# openSX70_chocolate_V341_20180103_manuall.net
KiCad netlist of a schematic drawn in EAGLE
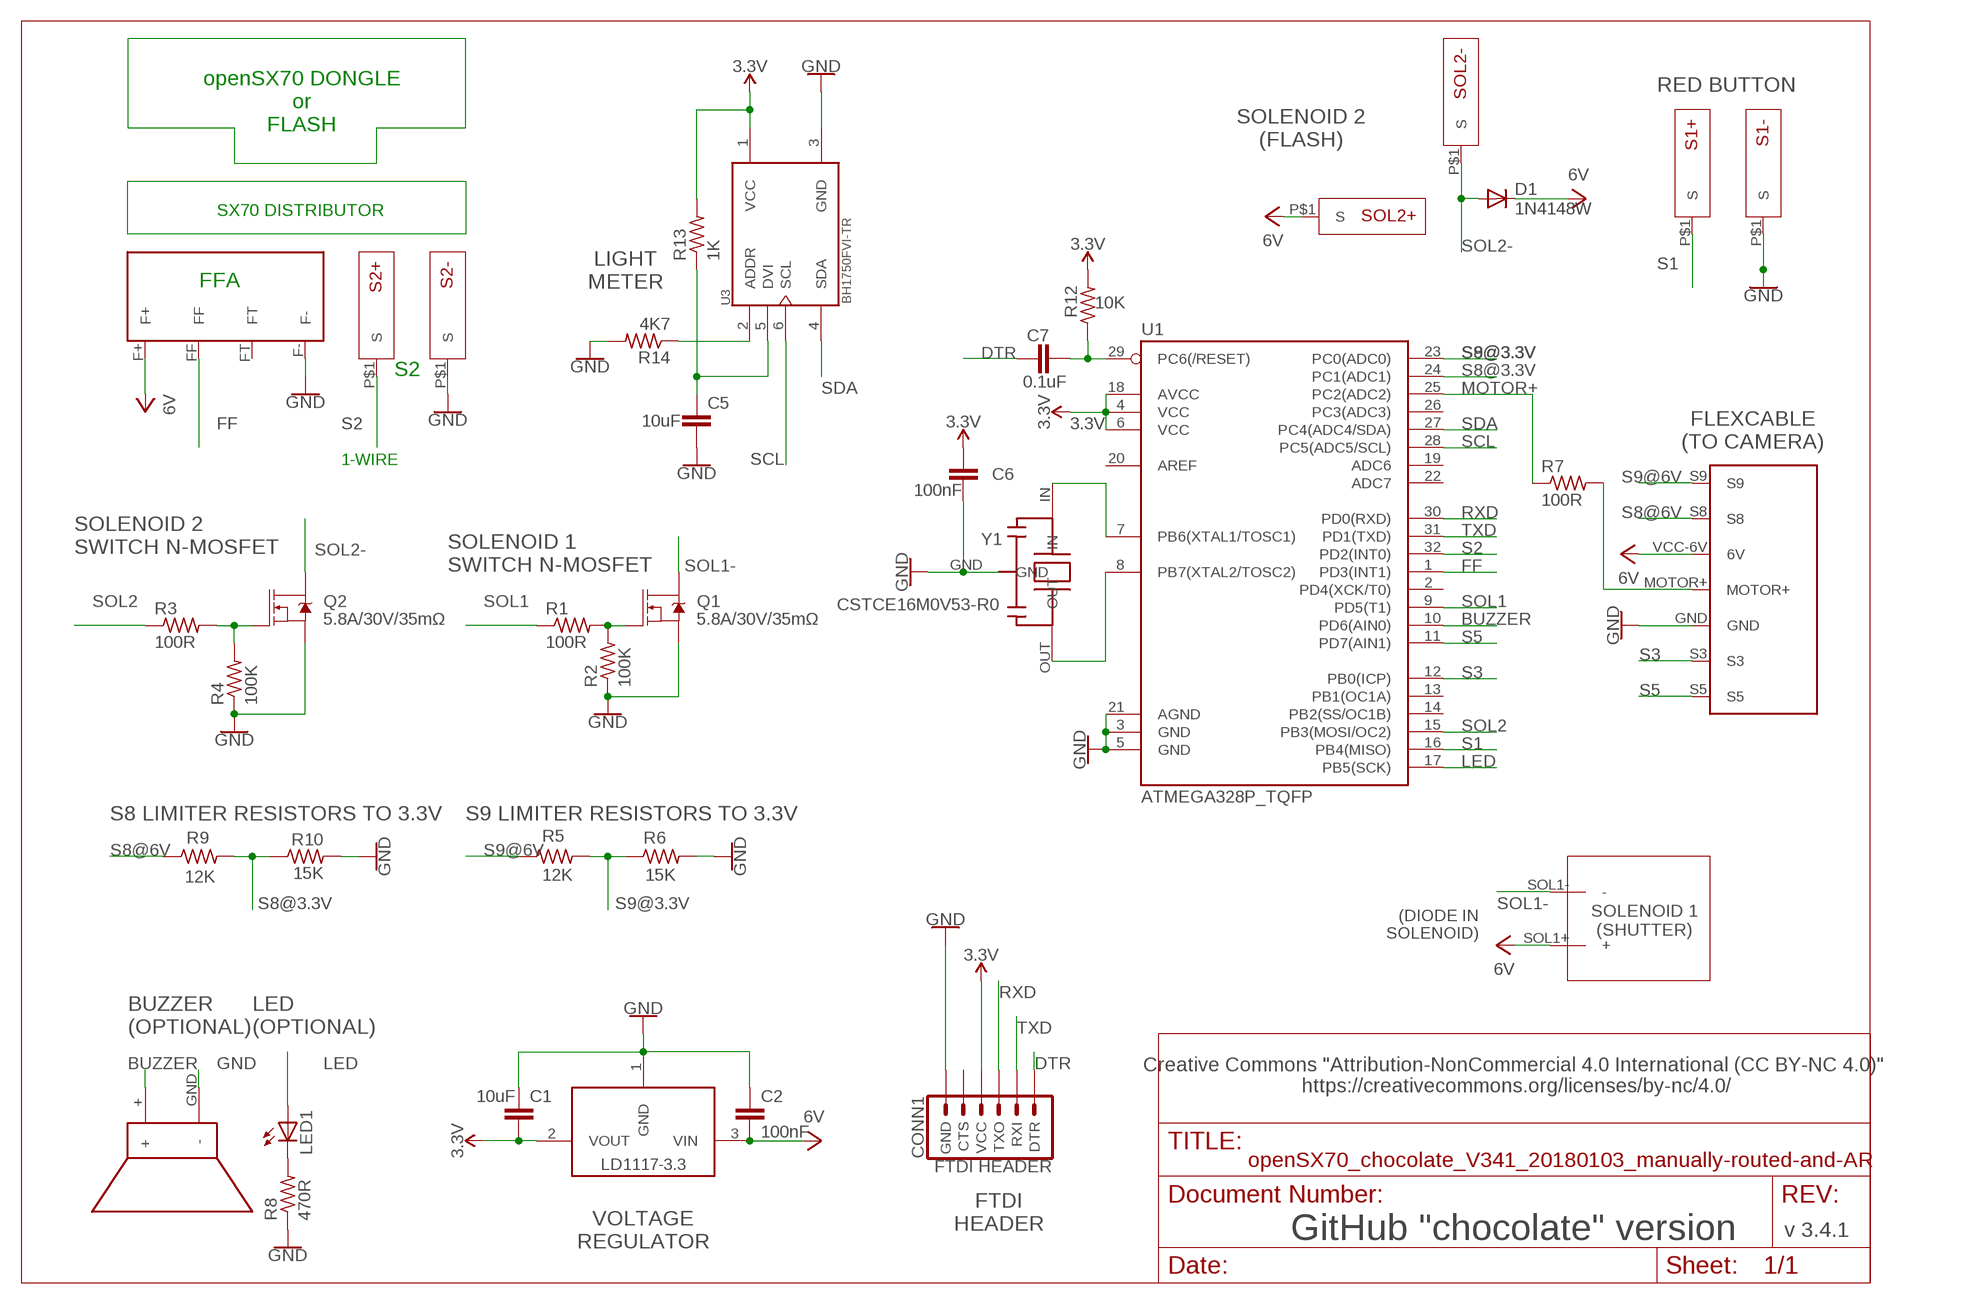
[diagram p0: schematic, sheet 1]

(export (version "E")
  (design (tool "Eeschema 10.0.6"))
  (components
    (comp (ref "BUZZ1")
      (value "CSET8-5G")
      (footprint "eagle-import:CSET8-5G_PACKAGE")
      (libsource (lib "eagle-import") (part "CSET8-5G"))
    )
    (comp (ref "C1")
      (value "10uF")
      (footprint "eagle-import:0603")
      (libsource (lib "eagle-import") (part "10UF-0603-6.3V-20%"))
    )
    (comp (ref "C2")
      (value "100nF")
      (footprint "eagle-import:C0603K")
      (libsource (lib "eagle-import") (part "C-EUC0603K"))
    )
    (comp (ref "C5")
      (value "10uF")
      (footprint "eagle-import:0603")
      (libsource (lib "eagle-import") (part "10UF-0603-6.3V-20%"))
    )
    (comp (ref "C6")
      (value "100nF")
      (footprint "eagle-import:C0805")
      (libsource (lib "eagle-import") (part "resistor_C-EUC0805"))
    )
    (comp (ref "C7")
      (value "0.1uF")
      (footprint "eagle-import:0603")
      (libsource (lib "eagle-import") (part "0.1UF-0603-25V-(+80/-20%)"))
    )
    (comp (ref "CONN1")
      (value "FTDI HEADER")
      (footprint "eagle-import:1X06")
      (libsource (lib "eagle-import") (part "6_PIN_SERIAL_TARGET"))
    )
    (comp (ref "D1")
      (value "1N4148W")
      (footprint "eagle-import:SOD-123_MINI-SMA")
      (libsource (lib "eagle-import") (part "CGRM400-G1"))
    )
    (comp (ref "LD11173.3V")
      (value "LD1117 3.3V")
      (footprint "eagle-import:SOT223")
      (fields (field (name "MF") "Advanced Monolithic Systems") (field (name "MP") "AMS1117-5.0"))
      (libsource (lib "eagle-import") (part "LD1117-3.3"))
    )
    (comp (ref "LED1")
      (value "LEDCHIPLED_0805")
      (footprint "eagle-import:CHIPLED_0805")
      (libsource (lib "eagle-import") (part "LEDCHIPLED_0805"))
    )
    (comp (ref "Q1")
      (value "5.8A/30V/35mΩ")
      (footprint "eagle-import:SOT23-3")
      (libsource (lib "eagle-import") (part "MOSFET-NCH-AO3404A"))
    )
    (comp (ref "Q2")
      (value "5.8A/30V/35mΩ")
      (footprint "eagle-import:SOT23-3")
      (libsource (lib "eagle-import") (part "MOSFET-NCH-AO3404A"))
    )
    (comp (ref "R1")
      (value "100R")
      (footprint "eagle-import:R0603")
      (libsource (lib "eagle-import") (part "R-US_R0603"))
    )
    (comp (ref "R2")
      (value "100K")
      (footprint "eagle-import:R0603")
      (libsource (lib "eagle-import") (part "R-US_R0603"))
    )
    (comp (ref "R3")
      (value "100R")
      (footprint "eagle-import:R0603")
      (libsource (lib "eagle-import") (part "R-US_R0603"))
    )
    (comp (ref "R4")
      (value "100K")
      (footprint "eagle-import:R0603")
      (libsource (lib "eagle-import") (part "R-US_R0603"))
    )
    (comp (ref "R5")
      (value "12K")
      (footprint "eagle-import:R0603")
      (libsource (lib "eagle-import") (part "R-US_R0603"))
    )
    (comp (ref "R6")
      (value "15K")
      (footprint "eagle-import:R0603")
      (libsource (lib "eagle-import") (part "R-US_R0603"))
    )
    (comp (ref "R7")
      (value "100R")
      (footprint "eagle-import:R0603")
      (libsource (lib "eagle-import") (part "R-US_R0603"))
    )
    (comp (ref "R8")
      (value "470R")
      (footprint "eagle-import:R0603")
      (libsource (lib "eagle-import") (part "R-US_R0603"))
    )
    (comp (ref "R9")
      (value "12K")
      (footprint "eagle-import:R0603")
      (libsource (lib "eagle-import") (part "R-US_R0603"))
    )
    (comp (ref "R10")
      (value "15K")
      (footprint "eagle-import:R0603")
      (libsource (lib "eagle-import") (part "R-US_R0603"))
    )
    (comp (ref "R12")
      (value "10K")
      (footprint "eagle-import:R0603")
      (libsource (lib "eagle-import") (part "R-US_R0603"))
    )
    (comp (ref "R13")
      (value "1K")
      (footprint "eagle-import:R0603")
      (libsource (lib "eagle-import") (part "R-US_R0603"))
    )
    (comp (ref "R14")
      (value "4K7")
      (footprint "eagle-import:R0603")
      (libsource (lib "eagle-import") (part "R-US_R0603"))
    )
    (comp (ref "S1+")
      (value "SX70-S-PAD-NEW")
      (footprint "eagle-import:SX70-S-PAD2")
      (libsource (lib "eagle-import") (part "SX70-S-PAD-NEW"))
    )
    (comp (ref "S1-")
      (value "SX70-S-PAD-NEW")
      (footprint "eagle-import:SX70-S-PAD2")
      (libsource (lib "eagle-import") (part "SX70-S-PAD-NEW"))
    )
    (comp (ref "S2+")
      (value "SX70-S-PAD-NEW")
      (footprint "eagle-import:SX70-S-PAD2")
      (libsource (lib "eagle-import") (part "SX70-S-PAD-NEW"))
    )
    (comp (ref "S2-")
      (value "SX70-S-PAD-NEW")
      (footprint "eagle-import:SX70-S-PAD2")
      (libsource (lib "eagle-import") (part "SX70-S-PAD-NEW"))
    )
    (comp (ref "SOL1")
      (value "SX70-SOLENOID1-2PADS")
      (footprint "eagle-import:SX70-SOLENOID1-2")
      (libsource (lib "eagle-import") (part "SX70-SOLENOID1-2PADS"))
    )
    (comp (ref "SOL2+")
      (value "SX70-S-PAD-NEW")
      (footprint "eagle-import:SX70-S-PAD2")
      (libsource (lib "eagle-import") (part "SX70-S-PAD-NEW"))
    )
    (comp (ref "SOL2-")
      (value "SX70-S-PAD-NEW")
      (footprint "eagle-import:SX70-S-PAD2")
      (libsource (lib "eagle-import") (part "SX70-S-PAD-NEW"))
    )
    (comp (ref "U$1")
      (value "SX70-7-PAD")
      (footprint "eagle-import:SX70-7-PAD")
      (libsource (lib "eagle-import") (part "SX70-7-PAD"))
    )
    (comp (ref "U$2")
      (value "FFA")
      (footprint "eagle-import:FFA-PAD-PACKAGE")
      (libsource (lib "eagle-import") (part "SX70-FFA-PAD"))
    )
    (comp (ref "U1")
      (value "ATMEGA328P_TQFP")
      (footprint "eagle-import:TQFP32-08")
      (libsource (lib "eagle-import") (part "ATMEGA328P_TQFP"))
    )
    (comp (ref "U3")
      (value "BH1750FVI-TR")
      (footprint "eagle-import:SOTFL50P300X75-6N")
      (fields (field (name "MF") "Rohm"))
      (libsource (lib "eagle-import") (part "BH1750FVI-TR"))
    )
    (comp (ref "Y1")
      (value "CSTCE16M0V53-R0")
      (footprint "eagle-import:CFP95P160X100-3N")
      (fields (field (name "MF") "Murata"))
      (libsource (lib "eagle-import") (part "CSTCE16M0V53-R0"))
    )
  )
  (nets
    (net (code "1") (name "/BUZZER") (class "Default")
      (node (ref "BUZZ1") (pin "+") (pinfunction "+_+") (pintype "bidirectional"))
      (node (ref "U1") (pin "10") (pinfunction "PD6(AIN0)_10") (pintype "bidirectional"))
    )
    (net (code "2") (name "/DTR") (class "Default")
      (node (ref "C7") (pin "1") (pinfunction "1_1") (pintype "passive"))
      (node (ref "CONN1") (pin "1") (pinfunction "DTR_1") (pintype "passive"))
    )
    (net (code "3") (name "/FF") (class "Default")
      (node (ref "U$2") (pin "FF") (pinfunction "FF_FF") (pintype "bidirectional"))
      (node (ref "U1") (pin "1") (pinfunction "PD3(INT1)_1") (pintype "bidirectional"))
    )
    (net (code "4") (name "/LED") (class "Default")
      (node (ref "LED1") (pin "A") (pinfunction "A_A") (pintype "passive"))
      (node (ref "U1") (pin "17") (pinfunction "PB5(SCK)_17") (pintype "bidirectional"))
    )
    (net (code "5") (name "/MOTOR+") (class "Default")
      (node (ref "R7") (pin "1") (pinfunction "1_1") (pintype "passive"))
      (node (ref "U1") (pin "25") (pinfunction "PC2(ADC2)_25") (pintype "bidirectional"))
    )
    (net (code "6") (name "/RXD") (class "Default")
      (node (ref "CONN1") (pin "3") (pinfunction "TXO_3") (pintype "passive"))
      (node (ref "U1") (pin "30") (pinfunction "PD0(RXD)_30") (pintype "bidirectional"))
    )
    (net (code "7") (name "/S1") (class "Default")
      (node (ref "S1+") (pin "P$1") (pinfunction "S_P$1") (pintype "bidirectional"))
      (node (ref "U1") (pin "16") (pinfunction "PB4(MISO)_16") (pintype "bidirectional"))
    )
    (net (code "8") (name "/S2") (class "Default")
      (node (ref "S2+") (pin "P$1") (pinfunction "S_P$1") (pintype "bidirectional"))
      (node (ref "U1") (pin "32") (pinfunction "PD2(INT0)_32") (pintype "bidirectional"))
    )
    (net (code "9") (name "/S3") (class "Default")
      (node (ref "U$1") (pin "S3") (pinfunction "S3_S3") (pintype "bidirectional"))
      (node (ref "U1") (pin "12") (pinfunction "PB0(ICP)_12") (pintype "bidirectional"))
    )
    (net (code "10") (name "/S5") (class "Default")
      (node (ref "U$1") (pin "S5") (pinfunction "S5_S5") (pintype "bidirectional"))
      (node (ref "U1") (pin "11") (pinfunction "PD7(AIN1)_11") (pintype "bidirectional"))
    )
    (net (code "11") (name "/S8@3.3V") (class "Default")
      (node (ref "R10") (pin "1") (pinfunction "1_1") (pintype "passive"))
      (node (ref "R9") (pin "2") (pinfunction "2_2") (pintype "passive"))
      (node (ref "U1") (pin "24") (pinfunction "PC1(ADC1)_24") (pintype "bidirectional"))
    )
    (net (code "12") (name "/S8@6V") (class "Default")
      (node (ref "R9") (pin "1") (pinfunction "1_1") (pintype "passive"))
      (node (ref "U$1") (pin "S8") (pinfunction "S8_S8") (pintype "bidirectional"))
    )
    (net (code "13") (name "/S9@3.3V") (class "Default")
      (node (ref "R5") (pin "2") (pinfunction "2_2") (pintype "passive"))
      (node (ref "R6") (pin "1") (pinfunction "1_1") (pintype "passive"))
      (node (ref "U1") (pin "23") (pinfunction "PC0(ADC0)_23") (pintype "bidirectional"))
    )
    (net (code "14") (name "/S9@6V") (class "Default")
      (node (ref "R5") (pin "1") (pinfunction "1_1") (pintype "passive"))
      (node (ref "U$1") (pin "S9") (pinfunction "S9_S9") (pintype "bidirectional"))
    )
    (net (code "15") (name "/SCL") (class "Default")
      (node (ref "U1") (pin "28") (pinfunction "PC5(ADC5/SCL)_28") (pintype "bidirectional"))
      (node (ref "U3") (pin "6") (pinfunction "SCL_6") (pintype "input"))
    )
    (net (code "16") (name "/SDA") (class "Default")
      (node (ref "U1") (pin "27") (pinfunction "PC4(ADC4/SDA)_27") (pintype "bidirectional"))
      (node (ref "U3") (pin "4") (pinfunction "SDA_4") (pintype "bidirectional"))
    )
    (net (code "17") (name "/SOL1") (class "Default")
      (node (ref "R1") (pin "1") (pinfunction "1_1") (pintype "passive"))
      (node (ref "U1") (pin "9") (pinfunction "PD5(T1)_9") (pintype "bidirectional"))
    )
    (net (code "18") (name "/SOL1-") (class "Default")
      (node (ref "Q1") (pin "3") (pinfunction "D_3") (pintype "bidirectional"))
      (node (ref "SOL1") (pin "SOL1-") (pinfunction "-_SOL1-") (pintype "bidirectional"))
    )
    (net (code "19") (name "/SOL2") (class "Default")
      (node (ref "R3") (pin "1") (pinfunction "1_1") (pintype "passive"))
      (node (ref "U1") (pin "15") (pinfunction "PB3(MOSI/OC2)_15") (pintype "bidirectional"))
    )
    (net (code "20") (name "/SOL2-") (class "Default")
      (node (ref "D1") (pin "A") (pinfunction "A_A") (pintype "passive"))
      (node (ref "Q2") (pin "3") (pinfunction "D_3") (pintype "bidirectional"))
      (node (ref "SOL2-") (pin "P$1") (pinfunction "S_P$1") (pintype "bidirectional"))
    )
    (net (code "21") (name "/TXD") (class "Default")
      (node (ref "CONN1") (pin "2") (pinfunction "RXI_2") (pintype "passive"))
      (node (ref "U1") (pin "31") (pinfunction "PD1(TXD)_31") (pintype "bidirectional"))
    )
    (net (code "22") (name "3.3V") (class "Default")
      (node (ref "C1") (pin "2") (pinfunction "2_2") (pintype "passive"))
      (node (ref "C6") (pin "1") (pinfunction "1_1") (pintype "passive"))
      (node (ref "CONN1") (pin "4") (pinfunction "VCC_4") (pintype "passive"))
      (node (ref "LD11173.3V") (pin "2") (pinfunction "VOUT_2") (pintype "bidirectional"))
      (node (ref "R12") (pin "2") (pinfunction "2_2") (pintype "passive"))
      (node (ref "R13") (pin "2") (pinfunction "2_2") (pintype "passive"))
      (node (ref "U1") (pin "18") (pinfunction "AVCC_18") (pintype "bidirectional"))
      (node (ref "U1") (pin "4") (pinfunction "VCC_4") (pintype "bidirectional"))
      (node (ref "U1") (pin "6") (pinfunction "VCC_6") (pintype "bidirectional"))
      (node (ref "U3") (pin "1") (pinfunction "VCC_1") (pintype "power_in"))
    )
    (net (code "23") (name "6V") (class "Default")
      (node (ref "C2") (pin "2") (pinfunction "2_2") (pintype "passive"))
      (node (ref "D1") (pin "C") (pinfunction "C_C") (pintype "passive"))
      (node (ref "LD11173.3V") (pin "3") (pinfunction "VIN_3") (pintype "bidirectional"))
      (node (ref "SOL1") (pin "SOL1+") (pinfunction "+_SOL1+") (pintype "bidirectional"))
      (node (ref "SOL2+") (pin "P$1") (pinfunction "S_P$1") (pintype "bidirectional"))
      (node (ref "U$1") (pin "VCC-6V") (pinfunction "6V_VCC-6V") (pintype "bidirectional"))
      (node (ref "U$2") (pin "F+") (pinfunction "F+_F+") (pintype "bidirectional"))
    )
    (net (code "24") (name "GND") (class "Default")
      (node (ref "BUZZ1") (pin "GND") (pinfunction "-_GND") (pintype "bidirectional"))
      (node (ref "C1") (pin "1") (pinfunction "1_1") (pintype "passive"))
      (node (ref "C2") (pin "1") (pinfunction "1_1") (pintype "passive"))
      (node (ref "C5") (pin "2") (pinfunction "2_2") (pintype "passive"))
      (node (ref "C6") (pin "2") (pinfunction "2_2") (pintype "passive"))
      (node (ref "CONN1") (pin "6") (pinfunction "GND_6") (pintype "passive"))
      (node (ref "LD11173.3V") (pin "1") (pinfunction "GND_1") (pintype "bidirectional"))
      (node (ref "Q1") (pin "2") (pinfunction "S_2") (pintype "bidirectional"))
      (node (ref "Q2") (pin "2") (pinfunction "S_2") (pintype "bidirectional"))
      (node (ref "R10") (pin "2") (pinfunction "2_2") (pintype "passive"))
      (node (ref "R14") (pin "2") (pinfunction "2_2") (pintype "passive"))
      (node (ref "R2") (pin "1") (pinfunction "1_1") (pintype "passive"))
      (node (ref "R4") (pin "1") (pinfunction "1_1") (pintype "passive"))
      (node (ref "R6") (pin "2") (pinfunction "2_2") (pintype "passive"))
      (node (ref "R8") (pin "1") (pinfunction "1_1") (pintype "passive"))
      (node (ref "S1-") (pin "P$1") (pinfunction "S_P$1") (pintype "bidirectional"))
      (node (ref "S2-") (pin "P$1") (pinfunction "S_P$1") (pintype "bidirectional"))
      (node (ref "U$1") (pin "GND") (pinfunction "GND_GND") (pintype "bidirectional"))
      (node (ref "U$2") (pin "F-") (pinfunction "F-_F-") (pintype "bidirectional"))
      (node (ref "U1") (pin "21") (pinfunction "AGND_21") (pintype "bidirectional"))
      (node (ref "U1") (pin "3") (pinfunction "GND_3") (pintype "bidirectional"))
      (node (ref "U1") (pin "5") (pinfunction "GND_5") (pintype "bidirectional"))
      (node (ref "U3") (pin "3") (pinfunction "GND_3") (pintype "power_in"))
      (node (ref "Y1") (pin "GND") (pinfunction "GND_GND") (pintype "passive"))
    )
    (net (code "25") (name "Net-(LED1-PadC)") (class "Default")
      (node (ref "LED1") (pin "C") (pinfunction "C_C") (pintype "passive"))
      (node (ref "R8") (pin "2") (pinfunction "2_2") (pintype "passive"))
    )
    (net (code "26") (name "Net-(Q1-G)") (class "Default")
      (node (ref "Q1") (pin "1") (pinfunction "G_1") (pintype "bidirectional"))
      (node (ref "R1") (pin "2") (pinfunction "2_2") (pintype "passive"))
      (node (ref "R2") (pin "2") (pinfunction "2_2") (pintype "passive"))
    )
    (net (code "27") (name "Net-(Q2-G)") (class "Default")
      (node (ref "Q2") (pin "1") (pinfunction "G_1") (pintype "bidirectional"))
      (node (ref "R3") (pin "2") (pinfunction "2_2") (pintype "passive"))
      (node (ref "R4") (pin "2") (pinfunction "2_2") (pintype "passive"))
    )
    (net (code "28") (name "Net-(R7-Pad2)") (class "Default")
      (node (ref "R7") (pin "2") (pinfunction "2_2") (pintype "passive"))
      (node (ref "U$1") (pin "MOTOR+") (pinfunction "MOTOR+_MOTOR+") (pintype "bidirectional"))
    )
    (net (code "29") (name "Net-(U1-PB6(XTAL1{slash}TOSC1))") (class "Default")
      (node (ref "U1") (pin "7") (pinfunction "PB6(XTAL1/TOSC1)_7") (pintype "bidirectional"))
      (node (ref "Y1") (pin "IN") (pinfunction "IN_IN") (pintype "input"))
    )
    (net (code "30") (name "Net-(U1-PB7(XTAL2{slash}TOSC2))") (class "Default")
      (node (ref "U1") (pin "8") (pinfunction "PB7(XTAL2/TOSC2)_8") (pintype "bidirectional"))
      (node (ref "Y1") (pin "OUT") (pinfunction "OUT_OUT") (pintype "output"))
    )
    (net (code "31") (name "Net-(U1-PC6({slash}RESET))") (class "Default")
      (node (ref "C7") (pin "2") (pinfunction "2_2") (pintype "passive"))
      (node (ref "R12") (pin "1") (pinfunction "1_1") (pintype "passive"))
      (node (ref "U1") (pin "29") (pinfunction "PC6(/RESET)_29") (pintype "bidirectional"))
    )
    (net (code "32") (name "Net-(U3-ADDR)") (class "Default")
      (node (ref "R14") (pin "1") (pinfunction "1_1") (pintype "passive"))
      (node (ref "U3") (pin "2") (pinfunction "ADDR_2") (pintype "input"))
    )
    (net (code "33") (name "Net-(U3-DVI)") (class "Default")
      (node (ref "C5") (pin "1") (pinfunction "1_1") (pintype "passive"))
      (node (ref "R13") (pin "1") (pinfunction "1_1") (pintype "passive"))
      (node (ref "U3") (pin "5") (pinfunction "DVI_5") (pintype "input"))
    )
    (net (code "34") (name "unconnected-(CONN1-CTS-Pad5)") (class "Default")
      (node (ref "CONN1") (pin "5") (pinfunction "CTS_5") (pintype "passive"))
    )
    (net (code "35") (name "unconnected-(U$2-PadFT)") (class "Default")
      (node (ref "U$2") (pin "FT") (pinfunction "FT_FT") (pintype "bidirectional"))
    )
    (net (code "36") (name "unconnected-(U1-ADC6-Pad19)") (class "Default")
      (node (ref "U1") (pin "19") (pinfunction "ADC6_19") (pintype "bidirectional"))
    )
    (net (code "37") (name "unconnected-(U1-ADC7-Pad22)") (class "Default")
      (node (ref "U1") (pin "22") (pinfunction "ADC7_22") (pintype "bidirectional"))
    )
    (net (code "38") (name "unconnected-(U1-AREF-Pad20)") (class "Default")
      (node (ref "U1") (pin "20") (pinfunction "AREF_20") (pintype "bidirectional"))
    )
    (net (code "39") (name "unconnected-(U1-PB1(OC1A)-Pad13)") (class "Default")
      (node (ref "U1") (pin "13") (pinfunction "PB1(OC1A)_13") (pintype "bidirectional"))
    )
    (net (code "40") (name "unconnected-(U1-PB2(SS{slash}OC1B)-Pad14)") (class "Default")
      (node (ref "U1") (pin "14") (pinfunction "PB2(SS/OC1B)_14") (pintype "bidirectional"))
    )
    (net (code "41") (name "unconnected-(U1-PC3(ADC3)-Pad26)") (class "Default")
      (node (ref "U1") (pin "26") (pinfunction "PC3(ADC3)_26") (pintype "bidirectional"))
    )
    (net (code "42") (name "unconnected-(U1-PD4(XCK{slash}T0)-Pad2)") (class "Default")
      (node (ref "U1") (pin "2") (pinfunction "PD4(XCK/T0)_2") (pintype "bidirectional"))
    )
  )
)
